# PoE.net
KiCad netlist of a schematic drawn in EAGLE
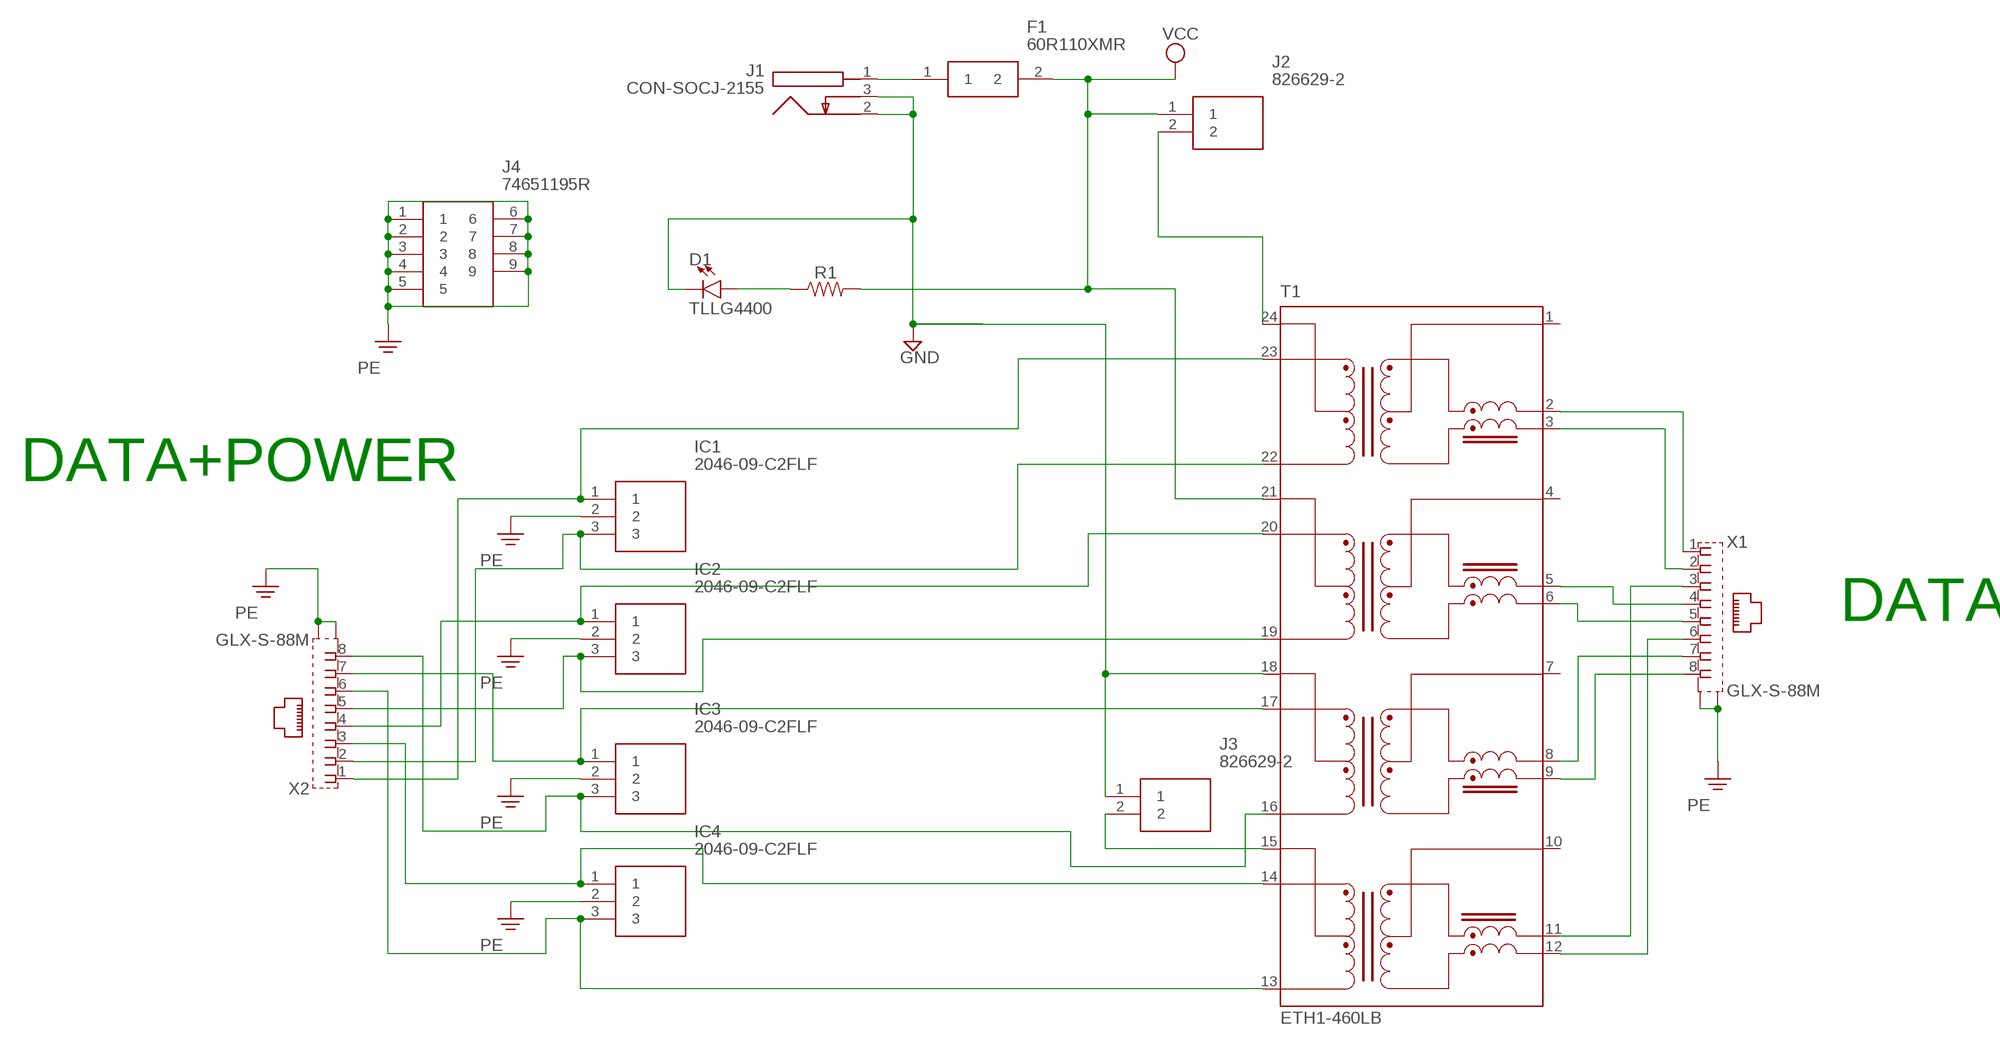
[diagram p0: schematic, sheet 1]

(export (version "E")
  (design (tool "Eeschema 10.0.6"))
  (components
    (comp (ref "D1")
      (value "TLLG4400")
      (footprint "eagle-import:LED_3MM")
      (libsource (lib "eagle-import") (part "LED3MM"))
    )
    (comp (ref "F1")
      (value "60R110XMR")
      (footprint "eagle-import:60R110XMR")
      (fields (field (name "MOUSER_PART_NUMBER") "576-60R110XMR"))
      (libsource (lib "eagle-import") (part "60R110XMR"))
    )
    (comp (ref "IC1")
      (value "2046-09-C2FLF")
      (footprint "eagle-import:204609C2FLF")
      (fields (field (name "MOUSER_PART_NUMBER") "652-2046-09-C2FLF"))
      (libsource (lib "eagle-import") (part "2046-09-C2FLF"))
    )
    (comp (ref "IC2")
      (value "2046-09-C2FLF")
      (footprint "eagle-import:204609C2FLF")
      (fields (field (name "MOUSER_PART_NUMBER") "652-2046-09-C2FLF"))
      (libsource (lib "eagle-import") (part "2046-09-C2FLF"))
    )
    (comp (ref "IC3")
      (value "2046-09-C2FLF")
      (footprint "eagle-import:204609C2FLF")
      (fields (field (name "MOUSER_PART_NUMBER") "652-2046-09-C2FLF"))
      (libsource (lib "eagle-import") (part "2046-09-C2FLF"))
    )
    (comp (ref "IC4")
      (value "2046-09-C2FLF")
      (footprint "eagle-import:204609C2FLF")
      (fields (field (name "MOUSER_PART_NUMBER") "652-2046-09-C2FLF"))
      (libsource (lib "eagle-import") (part "2046-09-C2FLF"))
    )
    (comp (ref "J1")
      (value "CON-SOCJ-2155")
      (footprint "eagle-import:CONSOCJ2155")
      (fields (field (name "MOUSER_PART_NUMBER") "992-CON-SOCJ-2155"))
      (libsource (lib "eagle-import") (part "CON-SOCJ-2155"))
    )
    (comp (ref "J2")
      (value "826629-2")
      (footprint "eagle-import:HDRV2W85P0X254_1X2_508X250X950")
      (fields (field (name "MOUSER_PART_NUMBER") "571-826629-2"))
      (libsource (lib "eagle-import") (part "826629-2"))
    )
    (comp (ref "J3")
      (value "826629-2")
      (footprint "eagle-import:HDRV2W85P0X254_1X2_508X250X950")
      (fields (field (name "MOUSER_PART_NUMBER") "571-826629-2"))
      (libsource (lib "eagle-import") (part "826629-2"))
    )
    (comp (ref "J4")
      (value "74651195R")
      (footprint "eagle-import:74651195R")
      (fields (field (name "MOUSER_PART_NUMBER") "710-74651195R"))
      (libsource (lib "eagle-import") (part "74651195R"))
    )
    (comp (ref "R1")
      (value "RESISTORAXIAL-0.3")
      (footprint "eagle-import:AXIAL-0.3")
      (libsource (lib "eagle-import") (part "RESISTORAXIAL-0.3"))
    )
    (comp (ref "T1")
      (value "ETH1-460LB")
      (footprint "eagle-import:XFMR_ETH1-460LB")
      (fields (field (name "MF") "Coilcraft"))
      (libsource (lib "eagle-import") (part "ETH1-460LB"))
    )
    (comp (ref "X1")
      (value "GLX-S-88M")
      (footprint "eagle-import:GLX-S-88M")
      (libsource (lib "eagle-import") (part "GLX-S-88M"))
    )
    (comp (ref "X2")
      (value "GLX-S-88M")
      (footprint "eagle-import:GLX-S-88M")
      (libsource (lib "eagle-import") (part "GLX-S-88M"))
    )
  )
  (nets
    (net (code "1") (name "GND") (class "Default")
      (node (ref "D1") (pin "K") (pinfunction "C_K") (pintype "passive"))
      (node (ref "J1") (pin "2") (pinfunction "2_2") (pintype "bidirectional"))
      (node (ref "J1") (pin "3") (pinfunction "3_3") (pintype "bidirectional"))
      (node (ref "J3") (pin "1") (pinfunction "1_1") (pintype "bidirectional"))
      (node (ref "T1") (pin "18") (pinfunction "TXCT_18_18") (pintype "passive"))
    )
    (net (code "2") (name "Net-(F1-Pad1)") (class "Default")
      (node (ref "F1") (pin "1") (pinfunction "1_1") (pintype "bidirectional"))
      (node (ref "J1") (pin "1") (pinfunction "1_1") (pintype "bidirectional"))
    )
    (net (code "3") (name "Net-(R1-1)") (class "Default")
      (node (ref "D1") (pin "A") (pinfunction "A_A") (pintype "passive"))
      (node (ref "R1") (pin "P$1") (pinfunction "1_P$1") (pintype "passive"))
    )
    (net (code "4") (name "Net-(T1-RX+_5)") (class "Default")
      (node (ref "T1") (pin "5") (pinfunction "RX+_5_5") (pintype "passive"))
      (node (ref "X1") (pin "4") (pinfunction "4_4") (pintype "passive"))
    )
    (net (code "5") (name "Net-(T1-RX+_11)") (class "Default")
      (node (ref "T1") (pin "11") (pinfunction "RX+_11_11") (pintype "passive"))
      (node (ref "X1") (pin "3") (pinfunction "3_3") (pintype "passive"))
    )
    (net (code "6") (name "Net-(T1-RX+_14)") (class "Default")
      (node (ref "IC4") (pin "1") (pinfunction "1_1") (pintype "bidirectional"))
      (node (ref "T1") (pin "14") (pinfunction "RX+_14_14") (pintype "passive"))
      (node (ref "X2") (pin "3") (pinfunction "3_3") (pintype "passive"))
    )
    (net (code "7") (name "Net-(T1-RX+_20)") (class "Default")
      (node (ref "IC2") (pin "1") (pinfunction "1_1") (pintype "bidirectional"))
      (node (ref "T1") (pin "20") (pinfunction "RX+_20_20") (pintype "passive"))
      (node (ref "X2") (pin "4") (pinfunction "4_4") (pintype "passive"))
    )
    (net (code "8") (name "Net-(T1-RX-_6)") (class "Default")
      (node (ref "T1") (pin "6") (pinfunction "RX-_6_6") (pintype "passive"))
      (node (ref "X1") (pin "5") (pinfunction "5_5") (pintype "passive"))
    )
    (net (code "9") (name "Net-(T1-RX-_12)") (class "Default")
      (node (ref "T1") (pin "12") (pinfunction "RX-_12_12") (pintype "passive"))
      (node (ref "X1") (pin "6") (pinfunction "6_6") (pintype "passive"))
    )
    (net (code "10") (name "Net-(T1-RX-_13)") (class "Default")
      (node (ref "IC4") (pin "3") (pinfunction "3_3") (pintype "bidirectional"))
      (node (ref "T1") (pin "13") (pinfunction "RX-_13_13") (pintype "passive"))
      (node (ref "X2") (pin "6") (pinfunction "6_6") (pintype "passive"))
    )
    (net (code "11") (name "Net-(T1-RX-_19)") (class "Default")
      (node (ref "IC2") (pin "3") (pinfunction "3_3") (pintype "bidirectional"))
      (node (ref "T1") (pin "19") (pinfunction "RX-_19_19") (pintype "passive"))
      (node (ref "X2") (pin "5") (pinfunction "5_5") (pintype "passive"))
    )
    (net (code "12") (name "Net-(T1-RXCT_15)") (class "Default")
      (node (ref "J3") (pin "2") (pinfunction "2_2") (pintype "bidirectional"))
      (node (ref "T1") (pin "15") (pinfunction "RXCT_15_15") (pintype "passive"))
    )
    (net (code "13") (name "Net-(T1-TX+_2)") (class "Default")
      (node (ref "T1") (pin "2") (pinfunction "TX+_2_2") (pintype "passive"))
      (node (ref "X1") (pin "1") (pinfunction "1_1") (pintype "passive"))
    )
    (net (code "14") (name "Net-(T1-TX+_8)") (class "Default")
      (node (ref "T1") (pin "8") (pinfunction "TX+_8_8") (pintype "passive"))
      (node (ref "X1") (pin "7") (pinfunction "7_7") (pintype "passive"))
    )
    (net (code "15") (name "Net-(T1-TX+_17)") (class "Default")
      (node (ref "IC3") (pin "1") (pinfunction "1_1") (pintype "bidirectional"))
      (node (ref "T1") (pin "17") (pinfunction "TX+_17_17") (pintype "passive"))
      (node (ref "X2") (pin "7") (pinfunction "7_7") (pintype "passive"))
    )
    (net (code "16") (name "Net-(T1-TX+_23)") (class "Default")
      (node (ref "IC1") (pin "1") (pinfunction "1_1") (pintype "bidirectional"))
      (node (ref "T1") (pin "23") (pinfunction "TX+_23_23") (pintype "passive"))
      (node (ref "X2") (pin "1") (pinfunction "1_1") (pintype "passive"))
    )
    (net (code "17") (name "Net-(T1-TX-_3)") (class "Default")
      (node (ref "T1") (pin "3") (pinfunction "TX-_3_3") (pintype "passive"))
      (node (ref "X1") (pin "2") (pinfunction "2_2") (pintype "passive"))
    )
    (net (code "18") (name "Net-(T1-TX-_9)") (class "Default")
      (node (ref "T1") (pin "9") (pinfunction "TX-_9_9") (pintype "passive"))
      (node (ref "X1") (pin "8") (pinfunction "8_8") (pintype "passive"))
    )
    (net (code "19") (name "Net-(T1-TX-_16)") (class "Default")
      (node (ref "IC3") (pin "3") (pinfunction "3_3") (pintype "bidirectional"))
      (node (ref "T1") (pin "16") (pinfunction "TX-_16_16") (pintype "passive"))
      (node (ref "X2") (pin "8") (pinfunction "8_8") (pintype "passive"))
    )
    (net (code "20") (name "Net-(T1-TXCT_24)") (class "Default")
      (node (ref "J2") (pin "2") (pinfunction "2_2") (pintype "bidirectional"))
      (node (ref "T1") (pin "24") (pinfunction "TXCT_24_24") (pintype "passive"))
    )
    (net (code "21") (name "Net-(T1-TX–_22)") (class "Default")
      (node (ref "IC1") (pin "3") (pinfunction "3_3") (pintype "bidirectional"))
      (node (ref "T1") (pin "22") (pinfunction "TX–_22_22") (pintype "passive"))
      (node (ref "X2") (pin "2") (pinfunction "2_2") (pintype "passive"))
    )
    (net (code "22") (name "PE") (class "Default")
      (node (ref "IC1") (pin "2") (pinfunction "2_2") (pintype "bidirectional"))
      (node (ref "IC2") (pin "2") (pinfunction "2_2") (pintype "bidirectional"))
      (node (ref "IC3") (pin "2") (pinfunction "2_2") (pintype "bidirectional"))
      (node (ref "IC4") (pin "2") (pinfunction "2_2") (pintype "bidirectional"))
      (node (ref "J4") (pin "1") (pinfunction "1_1") (pintype "bidirectional"))
      (node (ref "J4") (pin "2") (pinfunction "2_2") (pintype "bidirectional"))
      (node (ref "J4") (pin "3") (pinfunction "3_3") (pintype "bidirectional"))
      (node (ref "J4") (pin "4") (pinfunction "4_4") (pintype "bidirectional"))
      (node (ref "J4") (pin "5") (pinfunction "5_5") (pintype "bidirectional"))
      (node (ref "J4") (pin "6") (pinfunction "6_6") (pintype "bidirectional"))
      (node (ref "J4") (pin "7") (pinfunction "7_7") (pintype "bidirectional"))
      (node (ref "J4") (pin "8") (pinfunction "8_8") (pintype "bidirectional"))
      (node (ref "J4") (pin "9") (pinfunction "9_9") (pintype "bidirectional"))
      (node (ref "X1") (pin "S1") (pinfunction "S1_S1") (pintype "passive"))
      (node (ref "X1") (pin "S2") (pinfunction "S2_S2") (pintype "passive"))
      (node (ref "X2") (pin "S1") (pinfunction "S1_S1") (pintype "passive"))
      (node (ref "X2") (pin "S2") (pinfunction "S2_S2") (pintype "passive"))
    )
    (net (code "23") (name "VCC") (class "Default")
      (node (ref "F1") (pin "2") (pinfunction "2_2") (pintype "bidirectional"))
      (node (ref "J2") (pin "1") (pinfunction "1_1") (pintype "bidirectional"))
      (node (ref "R1") (pin "P$2") (pinfunction "2_P$2") (pintype "passive"))
      (node (ref "T1") (pin "21") (pinfunction "RXCT_21_21") (pintype "passive"))
    )
    (net (code "24") (name "unconnected-(T1-RXCT_4-Pad4)") (class "Default")
      (node (ref "T1") (pin "4") (pinfunction "RXCT_4_4") (pintype "passive"))
    )
    (net (code "25") (name "unconnected-(T1-RXCT_10-Pad10)") (class "Default")
      (node (ref "T1") (pin "10") (pinfunction "RXCT_10_10") (pintype "passive"))
    )
    (net (code "26") (name "unconnected-(T1-TXCT_1-Pad1)") (class "Default")
      (node (ref "T1") (pin "1") (pinfunction "TXCT_1_1") (pintype "passive"))
    )
    (net (code "27") (name "unconnected-(T1-TXCT_7-Pad7)") (class "Default")
      (node (ref "T1") (pin "7") (pinfunction "TXCT_7_7") (pintype "passive"))
    )
  )
)
